# ECU_AutoRC_BLE_r00.net
KiCad netlist of a schematic drawn in Altium Designer
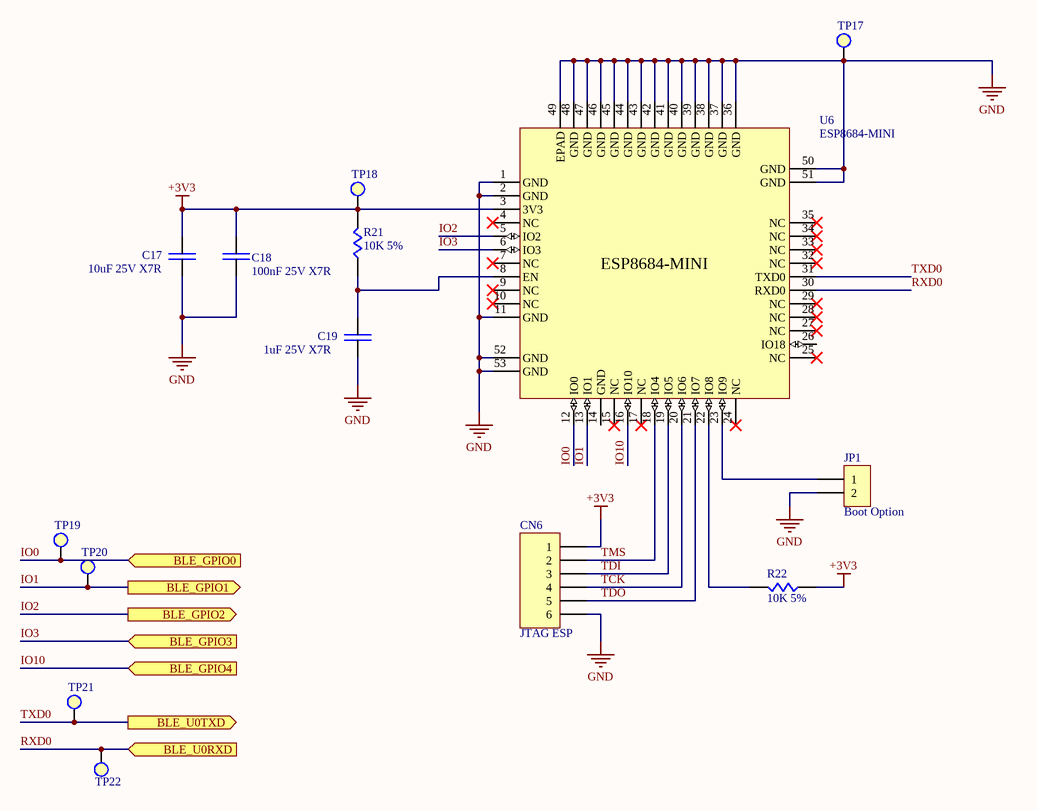
[diagram p0: ECU_AutoRC_BLE_r00.SchDoc]

(export (version "E")
  (design (tool "Eeschema 10.0.6"))
  (components
    (comp (ref "C17")
      (value "10uF 25V X7R")
      (footprint "C_0805")
      (description "Non Polarizated Capacitor")
      (libsource (lib "ECU_AutoRC_r00") (part "Capacitor NP"))
    )
    (comp (ref "C18")
      (value "100nF 25V X7R")
      (footprint "C_0805")
      (description "Non Polarizated Capacitor")
      (libsource (lib "ECU_AutoRC_r00") (part "Capacitor NP"))
    )
    (comp (ref "C19")
      (value "1uF 25V X7R")
      (footprint "C_0805")
      (description "Non Polarizated Capacitor")
      (libsource (lib "ECU_AutoRC_r00") (part "Capacitor NP"))
    )
    (comp (ref "CN6")
      (value "JTAG ESP")
      (footprint "HEADER_2x3_2.5MM")
      (description "Connector Generic 6 Vias")
      (libsource (lib "ECU_AutoRC_r00") (part "CONN_06P"))
    )
    (comp (ref "JP1")
      (value "Boot Option")
      (footprint "Header_M_1x2_0.1\"")
      (libsource (lib "ECU_AutoRC_r00") (part "Jumper"))
    )
    (comp (ref "R21")
      (value "10K 5%")
      (footprint "R_0805")
      (description "Resistor")
      (libsource (lib "ECU_AutoRC_r00") (part "Resistor"))
    )
    (comp (ref "R22")
      (value "10K 5%")
      (footprint "R_0805")
      (description "Resistor")
      (libsource (lib "ECU_AutoRC_r00") (part "Resistor"))
    )
    (comp (ref "TP17")
      (value "Test Point")
      (footprint "TEST_POINT")
      (libsource (lib "ECU_AutoRC_r00") (part "TestPoint"))
    )
    (comp (ref "TP18")
      (value "Test Point")
      (footprint "TEST_POINT")
      (libsource (lib "ECU_AutoRC_r00") (part "TestPoint"))
    )
    (comp (ref "TP19")
      (value "Test Point")
      (footprint "TEST_POINT")
      (libsource (lib "ECU_AutoRC_r00") (part "TestPoint"))
    )
    (comp (ref "TP20")
      (value "Test Point")
      (footprint "TEST_POINT")
      (libsource (lib "ECU_AutoRC_r00") (part "TestPoint"))
    )
    (comp (ref "TP21")
      (value "Test Point")
      (footprint "TEST_POINT")
      (libsource (lib "ECU_AutoRC_r00") (part "TestPoint"))
    )
    (comp (ref "TP22")
      (value "Test Point")
      (footprint "TEST_POINT")
      (libsource (lib "ECU_AutoRC_r00") (part "TestPoint"))
    )
    (comp (ref "U6")
      (value "ESP8684-MINI")
      (footprint "ESP8684-MINI")
      (libsource (lib "ECU_AutoRC_r00") (part "ESP8684-MINI"))
    )
  )
  (nets
    (net (code "1") (name "+3V3") (class "Default")
      (node (ref "C17") (pin "1") (pinfunction "1_1") (pintype "passive"))
      (node (ref "C18") (pin "1") (pinfunction "1_1") (pintype "passive"))
      (node (ref "CN6") (pin "1") (pinfunction "1_1") (pintype "passive"))
      (node (ref "R21") (pin "2") (pinfunction "2_2") (pintype "passive"))
      (node (ref "R22") (pin "1") (pinfunction "1_1") (pintype "passive"))
      (node (ref "TP18") (pin "1") (pintype "passive"))
      (node (ref "U6") (pin "3") (pinfunction "3V3_3") (pintype "passive"))
    )
    (net (code "2") (name "/IO0") (class "Default")
      (node (ref "TP19") (pin "1") (pintype "passive"))
      (node (ref "U6") (pin "12") (pinfunction "IO0_12") (pintype "bidirectional"))
    )
    (net (code "3") (name "/IO1") (class "Default")
      (node (ref "TP20") (pin "1") (pintype "passive"))
      (node (ref "U6") (pin "13") (pinfunction "IO1_13") (pintype "bidirectional"))
    )
    (net (code "4") (name "/IO2") (class "Default")
      (node (ref "U6") (pin "5") (pinfunction "IO2_5") (pintype "bidirectional"))
    )
    (net (code "5") (name "/IO3") (class "Default")
      (node (ref "U6") (pin "6") (pinfunction "IO3_6") (pintype "bidirectional"))
    )
    (net (code "6") (name "/IO10") (class "Default")
      (node (ref "U6") (pin "16") (pinfunction "IO10_16") (pintype "bidirectional"))
    )
    (net (code "7") (name "/RXD0") (class "Default")
      (node (ref "TP22") (pin "1") (pintype "passive"))
      (node (ref "U6") (pin "30") (pinfunction "RXD0_30") (pintype "passive"))
    )
    (net (code "8") (name "/TCK") (class "Default")
      (node (ref "CN6") (pin "4") (pinfunction "4_4") (pintype "passive"))
      (node (ref "U6") (pin "20") (pinfunction "IO6_20") (pintype "bidirectional"))
    )
    (net (code "9") (name "/TDI") (class "Default")
      (node (ref "CN6") (pin "3") (pinfunction "3_3") (pintype "passive"))
      (node (ref "U6") (pin "19") (pinfunction "IO5_19") (pintype "bidirectional"))
    )
    (net (code "10") (name "/TDO") (class "Default")
      (node (ref "CN6") (pin "5") (pinfunction "5_5") (pintype "passive"))
      (node (ref "U6") (pin "21") (pinfunction "IO7_21") (pintype "bidirectional"))
    )
    (net (code "11") (name "/TMS") (class "Default")
      (node (ref "CN6") (pin "2") (pinfunction "2_2") (pintype "passive"))
      (node (ref "U6") (pin "18") (pinfunction "IO4_18") (pintype "bidirectional"))
    )
    (net (code "12") (name "/TXD0") (class "Default")
      (node (ref "TP21") (pin "1") (pintype "passive"))
      (node (ref "U6") (pin "31") (pinfunction "TXD0_31") (pintype "passive"))
    )
    (net (code "13") (name "GND") (class "Default")
      (node (ref "C17") (pin "2") (pinfunction "2_2") (pintype "passive"))
      (node (ref "C18") (pin "2") (pinfunction "2_2") (pintype "passive"))
      (node (ref "C19") (pin "2") (pinfunction "2_2") (pintype "passive"))
      (node (ref "CN6") (pin "6") (pinfunction "6_6") (pintype "passive"))
      (node (ref "JP1") (pin "2") (pinfunction "2_2") (pintype "passive"))
      (node (ref "TP17") (pin "1") (pintype "passive"))
      (node (ref "U6") (pin "1") (pinfunction "GND_1") (pintype "passive"))
      (node (ref "U6") (pin "11") (pinfunction "GND_11") (pintype "passive"))
      (node (ref "U6") (pin "2") (pinfunction "GND_2") (pintype "passive"))
      (node (ref "U6") (pin "36") (pinfunction "GND_36") (pintype "passive"))
      (node (ref "U6") (pin "37") (pinfunction "GND_37") (pintype "passive"))
      (node (ref "U6") (pin "38") (pinfunction "GND_38") (pintype "passive"))
      (node (ref "U6") (pin "39") (pinfunction "GND_39") (pintype "passive"))
      (node (ref "U6") (pin "40") (pinfunction "GND_40") (pintype "passive"))
      (node (ref "U6") (pin "41") (pinfunction "GND_41") (pintype "passive"))
      (node (ref "U6") (pin "42") (pinfunction "GND_42") (pintype "passive"))
      (node (ref "U6") (pin "43") (pinfunction "GND_43") (pintype "passive"))
      (node (ref "U6") (pin "44") (pinfunction "GND_44") (pintype "passive"))
      (node (ref "U6") (pin "45") (pinfunction "GND_45") (pintype "passive"))
      (node (ref "U6") (pin "46") (pinfunction "GND_46") (pintype "passive"))
      (node (ref "U6") (pin "47") (pinfunction "GND_47") (pintype "passive"))
      (node (ref "U6") (pin "48") (pinfunction "GND_48") (pintype "passive"))
      (node (ref "U6") (pin "49") (pinfunction "EPAD_49") (pintype "passive"))
      (node (ref "U6") (pin "50") (pinfunction "GND_50") (pintype "passive"))
      (node (ref "U6") (pin "51") (pinfunction "GND_51") (pintype "passive"))
      (node (ref "U6") (pin "52") (pinfunction "GND_52") (pintype "passive"))
      (node (ref "U6") (pin "53") (pinfunction "GND_53") (pintype "passive"))
    )
    (net (code "14") (name "Net-(U6-EN)") (class "Default")
      (node (ref "C19") (pin "1") (pinfunction "1_1") (pintype "passive"))
      (node (ref "R21") (pin "1") (pinfunction "1_1") (pintype "passive"))
      (node (ref "U6") (pin "8") (pinfunction "EN_8") (pintype "passive"))
    )
    (net (code "15") (name "Net-(U6-IO8)") (class "Default")
      (node (ref "R22") (pin "2") (pinfunction "2_2") (pintype "passive"))
      (node (ref "U6") (pin "22") (pinfunction "IO8_22") (pintype "bidirectional"))
    )
    (net (code "16") (name "Net-(U6-IO9)") (class "Default")
      (node (ref "JP1") (pin "1") (pinfunction "1_1") (pintype "passive"))
      (node (ref "U6") (pin "23") (pinfunction "IO9_23") (pintype "bidirectional"))
    )
    (net (code "17") (name "unconnected-(U6-GND-Pad14)") (class "Default")
      (node (ref "U6") (pin "14") (pinfunction "GND_14") (pintype "passive"))
    )
    (net (code "18") (name "unconnected-(U6-IO18-Pad26)") (class "Default")
      (node (ref "U6") (pin "26") (pinfunction "IO18_26") (pintype "bidirectional"))
    )
    (net (code "19") (name "unconnected-(U6-NC-Pad4)") (class "Default")
      (node (ref "U6") (pin "4") (pinfunction "NC_4") (pintype "passive+no_connect"))
    )
    (net (code "20") (name "unconnected-(U6-NC-Pad7)") (class "Default")
      (node (ref "U6") (pin "7") (pinfunction "NC_7") (pintype "passive+no_connect"))
    )
    (net (code "21") (name "unconnected-(U6-NC-Pad9)") (class "Default")
      (node (ref "U6") (pin "9") (pinfunction "NC_9") (pintype "passive+no_connect"))
    )
    (net (code "22") (name "unconnected-(U6-NC-Pad10)") (class "Default")
      (node (ref "U6") (pin "10") (pinfunction "NC_10") (pintype "passive+no_connect"))
    )
    (net (code "23") (name "unconnected-(U6-NC-Pad15)") (class "Default")
      (node (ref "U6") (pin "15") (pinfunction "NC_15") (pintype "passive+no_connect"))
    )
    (net (code "24") (name "unconnected-(U6-NC-Pad17)") (class "Default")
      (node (ref "U6") (pin "17") (pinfunction "NC_17") (pintype "passive+no_connect"))
    )
    (net (code "25") (name "unconnected-(U6-NC-Pad24)") (class "Default")
      (node (ref "U6") (pin "24") (pinfunction "NC_24") (pintype "passive+no_connect"))
    )
    (net (code "26") (name "unconnected-(U6-NC-Pad25)") (class "Default")
      (node (ref "U6") (pin "25") (pinfunction "NC_25") (pintype "passive+no_connect"))
    )
    (net (code "27") (name "unconnected-(U6-NC-Pad27)") (class "Default")
      (node (ref "U6") (pin "27") (pinfunction "NC_27") (pintype "passive+no_connect"))
    )
    (net (code "28") (name "unconnected-(U6-NC-Pad28)") (class "Default")
      (node (ref "U6") (pin "28") (pinfunction "NC_28") (pintype "passive+no_connect"))
    )
    (net (code "29") (name "unconnected-(U6-NC-Pad29)") (class "Default")
      (node (ref "U6") (pin "29") (pinfunction "NC_29") (pintype "passive+no_connect"))
    )
    (net (code "30") (name "unconnected-(U6-NC-Pad32)") (class "Default")
      (node (ref "U6") (pin "32") (pinfunction "NC_32") (pintype "passive+no_connect"))
    )
    (net (code "31") (name "unconnected-(U6-NC-Pad33)") (class "Default")
      (node (ref "U6") (pin "33") (pinfunction "NC_33") (pintype "passive+no_connect"))
    )
    (net (code "32") (name "unconnected-(U6-NC-Pad34)") (class "Default")
      (node (ref "U6") (pin "34") (pinfunction "NC_34") (pintype "passive+no_connect"))
    )
    (net (code "33") (name "unconnected-(U6-NC-Pad35)") (class "Default")
      (node (ref "U6") (pin "35") (pinfunction "NC_35") (pintype "passive+no_connect"))
    )
  )
)
